# MCU098_04_XDS110-ET_EnergyTrace.net
KiCad netlist of a schematic drawn in Altium Designer
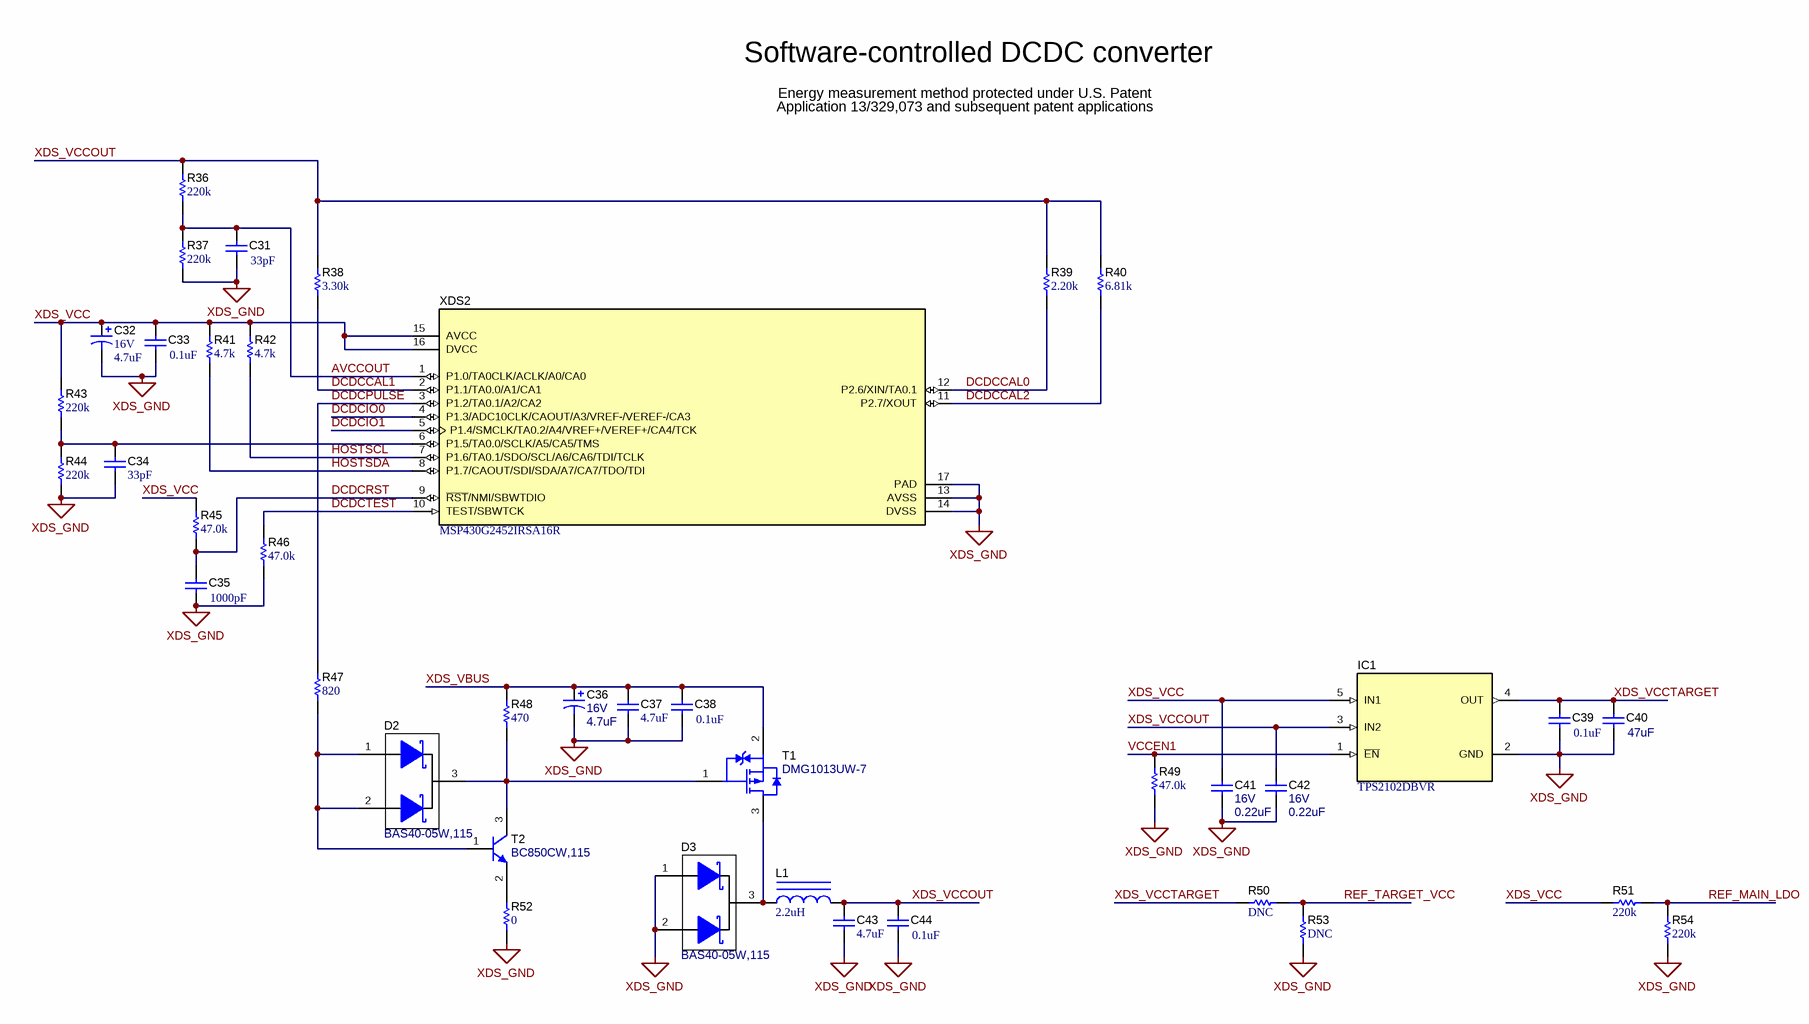
[diagram p0: MCU098_04_XDS110-ET_EnergyTrace.SchDoc]

(export (version "E")
  (design (tool "Eeschema 10.0.6"))
  (components
    (comp (ref "C31")
      (value "GRM1555C1H330JA01D")
      (footprint "0402")
      (description "CAP, CERM, 33 pF, 50 V, +/- 5%, C0G/NP0, 0402")
      (fields
        (field (name "MANUFACTURER") "MuRata")
        (field (name "VALUEDISPLAYED") "33pF")
        (field (name "PUBLISHER") "Texas Instruments")
      )
      (libsource (lib "Altium Vault - TI") (part "Capacitor"))
    )
    (comp (ref "C32")
      (value "TAJA475K016RNJ")
      (footprint "3216-18")
      (description "CAP, TA, 4.7 uF, 16 V, +/- 10%, 4 ohm, SMD")
      (fields
        (field (name "MANUFACTURER") "AVX")
        (field (name "VDC_V") "16V")
        (field (name "VALUEDISPLAYED") "4.7uF")
        (field (name "PUBLISHER") "Texas Instruments")
      )
      (libsource (lib "Altium Vault - TI") (part "Cap_Polarized"))
    )
    (comp (ref "C33")
      (value "GRM155R70J104KA01D")
      (footprint "0402")
      (description "CAP, CERM, 0.1 uF, 6.3 V, +/- 10%, X7R, 0402")
      (fields
        (field (name "MANUFACTURER") "MuRata")
        (field (name "VALUEDISPLAYED") "0.1uF")
        (field (name "PUBLISHER") "Texas Instruments")
      )
      (libsource (lib "Altium Vault - TI") (part "Capacitor"))
    )
    (comp (ref "C34")
      (value "GRM1555C1H330JA01D")
      (footprint "0402")
      (description "CAP, CERM, 33 pF, 50 V, +/- 5%, C0G/NP0, 0402")
      (fields
        (field (name "MANUFACTURER") "MuRata")
        (field (name "VALUEDISPLAYED") "33pF")
        (field (name "PUBLISHER") "Texas Instruments")
      )
      (libsource (lib "Altium Vault - TI") (part "Capacitor"))
    )
    (comp (ref "C35")
      (value "GCM155R71H102KA37D")
      (footprint "0402")
      (description "CAP, CERM, 1000 pF, 50 V, +/- 10%, X7R, AEC-Q200 Grade 1, 0402")
      (fields
        (field (name "MANUFACTURER") "MuRata")
        (field (name "VALUEDISPLAYED") "1000pF")
        (field (name "PUBLISHER") "Texas Instruments")
      )
      (libsource (lib "Altium Vault - TI") (part "Capacitor"))
    )
    (comp (ref "C36")
      (value "TAJA475K016RNJ")
      (footprint "3216-18")
      (description "CAP, TA, 4.7 uF, 16 V, +/- 10%, 4 ohm, SMD")
      (fields
        (field (name "MANUFACTURER") "AVX")
        (field (name "VDC_V") "16V")
        (field (name "VALUEDISPLAYED") "4.7uF")
        (field (name "PUBLISHER") "Texas Instruments")
      )
      (libsource (lib "Altium Vault - TI") (part "Cap_Polarized"))
    )
    (comp (ref "C37")
      (value "GRM188R61C475KAAJ")
      (footprint "0603")
      (description "CAP, CERM, 4.7 uF, 16 V, +/- 10%, X5R, 0603")
      (fields
        (field (name "MANUFACTURER") "MuRata")
        (field (name "VALUEDISPLAYED") "4.7uF")
        (field (name "PUBLISHER") "Texas Instruments")
      )
      (libsource (lib "Altium Vault - TI") (part "Capacitor"))
    )
    (comp (ref "C38")
      (value "GRM155R70J104KA01D")
      (footprint "0402")
      (description "CAP, CERM, 0.1 uF, 6.3 V, +/- 10%, X7R, 0402")
      (fields
        (field (name "MANUFACTURER") "MuRata")
        (field (name "VALUEDISPLAYED") "0.1uF")
        (field (name "PUBLISHER") "Texas Instruments")
      )
      (libsource (lib "Altium Vault - TI") (part "Capacitor"))
    )
    (comp (ref "C39")
      (value "GRM155R70J104KA01D")
      (footprint "0402")
      (description "CAP, CERM, 0.1 uF, 6.3 V, +/- 10%, X7R, 0402")
      (fields
        (field (name "MANUFACTURER") "MuRata")
        (field (name "VALUEDISPLAYED") "0.1uF")
        (field (name "PUBLISHER") "Texas Instruments")
      )
      (libsource (lib "Altium Vault - TI") (part "Capacitor"))
    )
    (comp (ref "C40")
      (value "GRM188R60J476ME15D")
      (footprint "0603")
      (description "CAP, CERM, 47 uF, 6.3 V, +/- 20%, X5R, 0603")
      (fields
        (field (name "MANUFACTURER") "MuRata")
        (field (name "VALUEDISPLAYED") "47uF")
        (field (name "PUBLISHER") "Texas Instruments")
      )
      (libsource (lib "Altium Vault - TI") (part "Capacitor"))
    )
    (comp (ref "C41")
      (value "GRM155R71C224KA12D")
      (footprint "0402")
      (description "CAP, CERM, 0.22 uF, 16 V, +/- 10%, X7R, 0402")
      (fields
        (field (name "MANUFACTURER") "MuRata")
        (field (name "VDC_V") "16V")
        (field (name "VALUEDISPLAYED") "0.22uF")
        (field (name "PUBLISHER") "Texas Instruments")
      )
      (libsource (lib "Altium Vault - TI") (part "Capacitor"))
    )
    (comp (ref "C42")
      (value "GRM155R71C224KA12D")
      (footprint "0402")
      (description "CAP, CERM, 0.22 uF, 16 V, +/- 10%, X7R, 0402")
      (fields
        (field (name "MANUFACTURER") "MuRata")
        (field (name "VDC_V") "16V")
        (field (name "VALUEDISPLAYED") "0.22uF")
        (field (name "PUBLISHER") "Texas Instruments")
      )
      (libsource (lib "Altium Vault - TI") (part "Capacitor"))
    )
    (comp (ref "C43")
      (value "GRM188R61C475KAAJ")
      (footprint "0603")
      (description "CAP, CERM, 4.7 uF, 16 V, +/- 10%, X5R, 0603")
      (fields
        (field (name "MANUFACTURER") "MuRata")
        (field (name "VALUEDISPLAYED") "4.7uF")
        (field (name "PUBLISHER") "Texas Instruments")
      )
      (libsource (lib "Altium Vault - TI") (part "Capacitor"))
    )
    (comp (ref "C44")
      (value "GRM155R70J104KA01D")
      (footprint "0402")
      (description "CAP, CERM, 0.1 uF, 6.3 V, +/- 10%, X7R, 0402")
      (fields
        (field (name "MANUFACTURER") "MuRata")
        (field (name "VALUEDISPLAYED") "0.1uF")
        (field (name "PUBLISHER") "Texas Instruments")
      )
      (libsource (lib "Altium Vault - TI") (part "Capacitor"))
    )
    (comp (ref "D2")
      (value "BAS40-05W,115")
      (footprint "SOT-323")
      (description "Diode, Schottky, 40 V, 0.12 A, AEC-Q101, SOT-323")
      (fields (field (name "MANUFACTURER") "Nexperia") (field (name "PUBLISHER") "Texas Instruments"))
      (libsource (lib "Altium Vault - TI") (part "DIODE_SCHOTTKY_A1C3_A2C3"))
    )
    (comp (ref "D3")
      (value "BAS40-05W,115")
      (footprint "SOT-323")
      (description "Diode, Schottky, 40 V, 0.12 A, AEC-Q101, SOT-323")
      (fields (field (name "MANUFACTURER") "Nexperia") (field (name "PUBLISHER") "Texas Instruments"))
      (libsource (lib "Altium Vault - TI") (part "DIODE_SCHOTTKY_A1C3_A2C3"))
    )
    (comp (ref "IC1")
      (value "TPS2102DBVR")
      (footprint "DBV0005A_N")
      (fields
        (field (name "ALTERNATE PARTNUMBER") "TPS2102DBVT")
        (field (name "MANUFACTURER") "Texas Instruments")
        (field (name "PARTNUMBER") "TPS2102DBVR")
        (field (name "PUBLISHER") "Texas Instruments")
      )
      (libsource (lib "Altium Vault - TI") (part "TPS2102DBV"))
    )
    (comp (ref "L1")
      (value "CBC2518T2R2M")
      (footprint "CBC2518")
      (description "Inductor, Wirewound, Ceramic, 2.2 uH, 0.89 A, 0.13 ohm, SMD")
      (fields
        (field (name "MANUFACTURER") "Taiyo Yuden")
        (field (name "VALUEDISPLAYED") "2.2uH")
        (field (name "PUBLISHER") "Texas Instruments")
      )
      (libsource (lib "Altium Vault - TI") (part "Inductor_Iron"))
    )
    (comp (ref "R36")
      (value "RC0402FR-07220KL")
      (footprint "0402")
      (description "RES, 220 k, 1%, 0.0625 W, 0402")
      (fields
        (field (name "MANUFACTURER") "Yageo America")
        (field (name "VALUEDISPLAYED") "220k")
        (field (name "PUBLISHER") "Texas Instruments")
      )
      (libsource (lib "Altium Vault - TI") (part "Resistor"))
    )
    (comp (ref "R37")
      (value "RC0402FR-07220KL")
      (footprint "0402")
      (description "RES, 220 k, 1%, 0.0625 W, 0402")
      (fields
        (field (name "MANUFACTURER") "Yageo America")
        (field (name "VALUEDISPLAYED") "220k")
        (field (name "PUBLISHER") "Texas Instruments")
      )
      (libsource (lib "Altium Vault - TI") (part "Resistor"))
    )
    (comp (ref "R38")
      (value "ERJ-2RKF3301X")
      (footprint "0402")
      (description "RES, 3.30 k, 1%, 0.1 W, AEC-Q200 Grade 0, 0402")
      (fields
        (field (name "MANUFACTURER") "Panasonic")
        (field (name "VALUEDISPLAYED") "3.30k")
        (field (name "PUBLISHER") "Texas Instruments")
      )
      (libsource (lib "Altium Vault - TI") (part "Resistor"))
    )
    (comp (ref "R39")
      (value "CRCW04022K20FKED")
      (footprint "0402")
      (description "RES, 2.20 k, 1%, 0.063 W, 0402")
      (fields
        (field (name "MANUFACTURER") "Vishay-Dale")
        (field (name "VALUEDISPLAYED") "2.20k")
        (field (name "PUBLISHER") "Texas Instruments")
      )
      (libsource (lib "Altium Vault - TI") (part "Resistor"))
    )
    (comp (ref "R40")
      (value "CRCW04026K81FKED")
      (footprint "0402")
      (description "RES, 6.81 k, 1%, 0.063 W, 0402")
      (fields
        (field (name "MANUFACTURER") "Vishay-Dale")
        (field (name "VALUEDISPLAYED") "6.81k")
        (field (name "PUBLISHER") "Texas Instruments")
      )
      (libsource (lib "Altium Vault - TI") (part "Resistor"))
    )
    (comp (ref "R41")
      (value "CRCW04024K70JNED")
      (footprint "0402")
      (description "RES, 4.7 k, 5%, 0.063 W, 0402")
      (fields
        (field (name "MANUFACTURER") "Vishay-Dale")
        (field (name "VALUEDISPLAYED") "4.7k")
        (field (name "PUBLISHER") "Texas Instruments")
      )
      (libsource (lib "Altium Vault - TI") (part "Resistor"))
    )
    (comp (ref "R42")
      (value "CRCW04024K70JNED")
      (footprint "0402")
      (description "RES, 4.7 k, 5%, 0.063 W, 0402")
      (fields
        (field (name "MANUFACTURER") "Vishay-Dale")
        (field (name "VALUEDISPLAYED") "4.7k")
        (field (name "PUBLISHER") "Texas Instruments")
      )
      (libsource (lib "Altium Vault - TI") (part "Resistor"))
    )
    (comp (ref "R43")
      (value "RC0402FR-07220KL")
      (footprint "0402")
      (description "RES, 220 k, 1%, 0.0625 W, 0402")
      (fields
        (field (name "MANUFACTURER") "Yageo America")
        (field (name "VALUEDISPLAYED") "220k")
        (field (name "PUBLISHER") "Texas Instruments")
      )
      (libsource (lib "Altium Vault - TI") (part "Resistor"))
    )
    (comp (ref "R44")
      (value "RC0402FR-07220KL")
      (footprint "0402")
      (description "RES, 220 k, 1%, 0.0625 W, 0402")
      (fields
        (field (name "MANUFACTURER") "Yageo America")
        (field (name "VALUEDISPLAYED") "220k")
        (field (name "PUBLISHER") "Texas Instruments")
      )
      (libsource (lib "Altium Vault - TI") (part "Resistor"))
    )
    (comp (ref "R45")
      (value "RC0402FR-0747KL")
      (footprint "0402")
      (description "RES, 47.0 k, 1%, 0.0625 W, 0402")
      (fields
        (field (name "MANUFACTURER") "Yageo America")
        (field (name "VALUEDISPLAYED") "47.0k")
        (field (name "PUBLISHER") "Texas Instruments")
      )
      (libsource (lib "Altium Vault - TI") (part "Resistor"))
    )
    (comp (ref "R46")
      (value "RC0402FR-0747KL")
      (footprint "0402")
      (description "RES, 47.0 k, 1%, 0.0625 W, 0402")
      (fields
        (field (name "MANUFACTURER") "Yageo America")
        (field (name "VALUEDISPLAYED") "47.0k")
        (field (name "PUBLISHER") "Texas Instruments")
      )
      (libsource (lib "Altium Vault - TI") (part "Resistor"))
    )
    (comp (ref "R47")
      (value "RC0402FR-07820RL")
      (footprint "0402")
      (description "RES, 820, 1%, 0.063 W, 0402")
      (fields
        (field (name "MANUFACTURER") "Yageo America")
        (field (name "VALUEDISPLAYED") "820")
        (field (name "PUBLISHER") "Texas Instruments")
      )
      (libsource (lib "Altium Vault - TI") (part "Resistor"))
    )
    (comp (ref "R48")
      (value "CRCW0402470RJNED")
      (footprint "0402")
      (description "RES, 470, 5%, 0.063 W, 0402")
      (fields
        (field (name "MANUFACTURER") "Vishay-Dale")
        (field (name "VALUEDISPLAYED") "470")
        (field (name "PUBLISHER") "Texas Instruments")
      )
      (libsource (lib "Altium Vault - TI") (part "Resistor"))
    )
    (comp (ref "R49")
      (value "RC0402FR-0747KL")
      (footprint "0402")
      (description "RES, 47.0 k, 1%, 0.0625 W, 0402")
      (fields
        (field (name "MANUFACTURER") "Yageo America")
        (field (name "VALUEDISPLAYED") "47.0k")
        (field (name "PUBLISHER") "Texas Instruments")
      )
      (libsource (lib "Altium Vault - TI") (part "Resistor"))
    )
    (comp (ref "R50")
      (value "RC0402FR-07220KL")
      (footprint "0402")
      (description "RES, 220 k, 1%, 0.0625 W, 0402")
      (fields
        (field (name "MANUFACTURER") "Yageo America")
        (field (name "VALUEDISPLAYED") "DNC")
        (field (name "PUBLISHER") "Texas Instruments")
      )
      (libsource (lib "Altium Vault - TI") (part "Resistor"))
    )
    (comp (ref "R51")
      (value "RC0402FR-07220KL")
      (footprint "0402")
      (description "RES, 220 k, 1%, 0.0625 W, 0402")
      (fields
        (field (name "MANUFACTURER") "Yageo America")
        (field (name "VALUEDISPLAYED") "220k")
        (field (name "PUBLISHER") "Texas Instruments")
      )
      (libsource (lib "Altium Vault - TI") (part "Resistor"))
    )
    (comp (ref "R52")
      (value "RC0603JR-070RL")
      (footprint "0603")
      (description "RES, 0, 5%, 0.1 W, 0603")
      (fields (field (name "MANUFACTURER") "Yageo") (field (name "VALUEDISPLAYED") "0"))
      (libsource (lib "Altium Vault - TI") (part "Resistor"))
    )
    (comp (ref "R53")
      (value "RC0402FR-07220KL")
      (footprint "0402")
      (description "RES, 220 k, 1%, 0.0625 W, 0402")
      (fields
        (field (name "MANUFACTURER") "Yageo America")
        (field (name "VALUEDISPLAYED") "DNC")
        (field (name "PUBLISHER") "Texas Instruments")
      )
      (libsource (lib "Altium Vault - TI") (part "Resistor"))
    )
    (comp (ref "R54")
      (value "RC0402FR-07220KL")
      (footprint "0402")
      (description "RES, 220 k, 1%, 0.0625 W, 0402")
      (fields
        (field (name "MANUFACTURER") "Yageo America")
        (field (name "VALUEDISPLAYED") "220k")
        (field (name "PUBLISHER") "Texas Instruments")
      )
      (libsource (lib "Altium Vault - TI") (part "Resistor"))
    )
    (comp (ref "T1")
      (value "DMG1013UW-7")
      (footprint "SOT-323")
      (description "MOSFET, P-CH, -20 V, -0.82 A, SOT-323")
      (fields (field (name "MANUFACTURER") "Diodes Inc.") (field (name "PUBLISHER") "Texas Instruments"))
      (libsource (lib "Altium Vault - TI") (part "MOSFET_P_D3G1S2_PD"))
    )
    (comp (ref "T2")
      (value "BC850CW,115")
      (footprint "SOT-323")
      (description "Transistor, NPN, 45 V, 0.1 A, SOT-323")
      (fields
        (field (name "MANUFACTURER") "NXP Semiconductor")
        (field (name "PUBLISHER") "Texas Instruments")
      )
      (libsource (lib "Altium Vault - TI") (part "BJT_NPN_C3B1E2"))
    )
    (comp (ref "XDS2")
      (value "MSP430G2452IRSA16R")
      (footprint "RSA0016B")
      (description "MSP430G2x52, MSP430G2x12 Mixed Signal Microcontroller, RSA0016B (VQFN-16)")
      (fields
        (field (name "PARTNUMBER") "MSP430G2452IRSA16R")
        (field (name "MANUFACTURER") "Texas Instruments")
        (field (name "ALTERNATE PARTNUMBER") "MSP430G2452IRSA16T")
      )
      (libsource (lib "Altium Vault - TI") (part "MSP430G2452IRSA"))
    )
  )
  (nets
    (net (code "1") (name "/AVCCOUT") (class "Default")
      (node (ref "C31") (pin "1") (pinfunction "1_1") (pintype "passive"))
      (node (ref "R36") (pin "1") (pinfunction "1_1") (pintype "passive"))
      (node (ref "R37") (pin "2") (pinfunction "2_2") (pintype "passive"))
      (node (ref "XDS2") (pin "1") (pinfunction "P1.0/TA0CLK/ACLK/A0/CA0_1") (pintype "bidirectional"))
    )
    (net (code "2") (name "/DCDCCAL0") (class "Default")
      (node (ref "R39") (pin "1") (pinfunction "1_1") (pintype "passive"))
      (node (ref "XDS2") (pin "12") (pinfunction "P2.6/XIN/TA0.1_12") (pintype "bidirectional"))
    )
    (net (code "3") (name "/DCDCCAL1") (class "Default")
      (node (ref "R38") (pin "1") (pinfunction "1_1") (pintype "passive"))
      (node (ref "XDS2") (pin "2") (pinfunction "P1.1/TA0.0/A1/CA1_2") (pintype "bidirectional"))
    )
    (net (code "4") (name "/DCDCCAL2") (class "Default")
      (node (ref "R40") (pin "1") (pinfunction "1_1") (pintype "passive"))
      (node (ref "XDS2") (pin "11") (pinfunction "P2.7/XOUT_11") (pintype "bidirectional"))
    )
    (net (code "5") (name "/DCDCIO0") (class "Default")
      (node (ref "XDS2") (pin "4") (pinfunction "P1.3/ADC10CLK/CAOUT/A3/VREF-/VEREF-/CA3_4") (pintype "bidirectional"))
    )
    (net (code "6") (name "/DCDCIO1") (class "Default")
      (node (ref "XDS2") (pin "5") (pinfunction "P1.4/SMCLK/TA0.2/A4/VREF+/VEREF+/CA4/TCK_5") (pintype "bidirectional"))
    )
    (net (code "7") (name "/DCDCPULSE") (class "Default")
      (node (ref "R47") (pin "2") (pinfunction "2_2") (pintype "passive"))
      (node (ref "XDS2") (pin "3") (pinfunction "P1.2/TA0.1/A2/CA2_3") (pintype "bidirectional"))
    )
    (net (code "8") (name "/DCDCRST") (class "Default")
      (node (ref "C35") (pin "1") (pinfunction "1_1") (pintype "passive"))
      (node (ref "R45") (pin "1") (pinfunction "1_1") (pintype "passive"))
      (node (ref "XDS2") (pin "9") (pinfunction "~{RST}/NMI/SBWTDIO_9") (pintype "bidirectional"))
    )
    (net (code "9") (name "/DCDCTEST") (class "Default")
      (node (ref "R46") (pin "2") (pinfunction "2_2") (pintype "passive"))
      (node (ref "XDS2") (pin "10") (pinfunction "TEST/SBWTCK_10") (pintype "input"))
    )
    (net (code "10") (name "/HOSTSCL") (class "Default")
      (node (ref "R42") (pin "1") (pinfunction "1_1") (pintype "passive"))
      (node (ref "XDS2") (pin "7") (pinfunction "P1.6/TA0.1/SDO/SCL/A6/CA6/TDI/TCLK_7") (pintype "bidirectional"))
    )
    (net (code "11") (name "/HOSTSDA") (class "Default")
      (node (ref "R41") (pin "1") (pinfunction "1_1") (pintype "passive"))
      (node (ref "XDS2") (pin "8") (pinfunction "P1.7/CAOUT/SDI/SDA/A7/CA7/TDO/TDI_8") (pintype "bidirectional"))
    )
    (net (code "12") (name "/REF_MAIN_LDO") (class "Default")
      (node (ref "R51") (pin "1") (pinfunction "1_1") (pintype "passive"))
      (node (ref "R54") (pin "2") (pinfunction "2_2") (pintype "passive"))
    )
    (net (code "13") (name "/REF_TARGET_VCC") (class "Default")
      (node (ref "R50") (pin "1") (pinfunction "1_1") (pintype "passive"))
      (node (ref "R53") (pin "2") (pinfunction "2_2") (pintype "passive"))
    )
    (net (code "14") (name "/VCCEN1") (class "Default")
      (node (ref "IC1") (pin "1") (pinfunction "EN_1") (pintype "input"))
      (node (ref "R49") (pin "2") (pinfunction "2_2") (pintype "passive"))
    )
    (net (code "15") (name "/XDS_VBUS") (class "Default")
      (node (ref "C36") (pin "1") (pinfunction "+_1") (pintype "passive"))
      (node (ref "C37") (pin "2") (pinfunction "2_2") (pintype "passive"))
      (node (ref "C38") (pin "1") (pinfunction "1_1") (pintype "passive"))
      (node (ref "R48") (pin "2") (pinfunction "2_2") (pintype "passive"))
      (node (ref "T1") (pin "2") (pinfunction "S_2") (pintype "passive"))
    )
    (net (code "16") (name "/XDS_VCC") (class "Default")
      (node (ref "C32") (pin "1") (pinfunction "+_1") (pintype "passive"))
      (node (ref "C33") (pin "1") (pinfunction "1_1") (pintype "passive"))
      (node (ref "C41") (pin "1") (pinfunction "1_1") (pintype "passive"))
      (node (ref "IC1") (pin "5") (pinfunction "IN1_5") (pintype "input"))
      (node (ref "R41") (pin "2") (pinfunction "2_2") (pintype "passive"))
      (node (ref "R42") (pin "2") (pinfunction "2_2") (pintype "passive"))
      (node (ref "R43") (pin "2") (pinfunction "2_2") (pintype "passive"))
      (node (ref "R45") (pin "2") (pinfunction "2_2") (pintype "passive"))
      (node (ref "R51") (pin "2") (pinfunction "2_2") (pintype "passive"))
      (node (ref "XDS2") (pin "15") (pinfunction "AVCC_15") (pintype "power_in"))
      (node (ref "XDS2") (pin "16") (pinfunction "DVCC_16") (pintype "power_in"))
    )
    (net (code "17") (name "/XDS_VCCOUT") (class "Default")
      (node (ref "C42") (pin "1") (pinfunction "1_1") (pintype "passive"))
      (node (ref "C43") (pin "2") (pinfunction "2_2") (pintype "passive"))
      (node (ref "C44") (pin "1") (pinfunction "1_1") (pintype "passive"))
      (node (ref "IC1") (pin "3") (pinfunction "IN2_3") (pintype "input"))
      (node (ref "L1") (pin "2") (pinfunction "2_2") (pintype "passive"))
      (node (ref "R36") (pin "2") (pinfunction "2_2") (pintype "passive"))
      (node (ref "R38") (pin "2") (pinfunction "2_2") (pintype "passive"))
      (node (ref "R39") (pin "2") (pinfunction "2_2") (pintype "passive"))
      (node (ref "R40") (pin "2") (pinfunction "2_2") (pintype "passive"))
    )
    (net (code "18") (name "/XDS_VCCTARGET") (class "Default")
      (node (ref "C39") (pin "1") (pinfunction "1_1") (pintype "passive"))
      (node (ref "C40") (pin "1") (pinfunction "1_1") (pintype "passive"))
      (node (ref "IC1") (pin "4") (pinfunction "OUT_4") (pintype "output"))
      (node (ref "R50") (pin "2") (pinfunction "2_2") (pintype "passive"))
    )
    (net (code "19") (name "Net-(D2-K)") (class "Default")
      (node (ref "D2") (pin "3") (pinfunction "K_3") (pintype "passive"))
      (node (ref "R48") (pin "1") (pinfunction "1_1") (pintype "passive"))
      (node (ref "T1") (pin "1") (pinfunction "G_1") (pintype "passive"))
      (node (ref "T2") (pin "3") (pinfunction "C_3") (pintype "passive"))
    )
    (net (code "20") (name "Net-(D3-K)") (class "Default")
      (node (ref "D3") (pin "3") (pinfunction "K_3") (pintype "passive"))
      (node (ref "L1") (pin "1") (pinfunction "1_1") (pintype "passive"))
      (node (ref "T1") (pin "3") (pinfunction "D_3") (pintype "passive"))
    )
    (net (code "21") (name "Net-(T2-B)") (class "Default")
      (node (ref "D2") (pin "1") (pinfunction "A_1") (pintype "passive"))
      (node (ref "D2") (pin "2") (pinfunction "A_2") (pintype "passive"))
      (node (ref "R47") (pin "1") (pinfunction "1_1") (pintype "passive"))
      (node (ref "T2") (pin "1") (pinfunction "B_1") (pintype "passive"))
    )
    (net (code "22") (name "Net-(T2-E)") (class "Default")
      (node (ref "R52") (pin "2") (pinfunction "2_2") (pintype "passive"))
      (node (ref "T2") (pin "2") (pinfunction "E_2") (pintype "passive"))
    )
    (net (code "23") (name "Net-(XDS2-P1.5{slash}TA0.0{slash}SCLK{slash}A5{slash}CA5{slash}TMS)") (class "Default")
      (node (ref "C34") (pin "1") (pinfunction "1_1") (pintype "passive"))
      (node (ref "R43") (pin "1") (pinfunction "1_1") (pintype "passive"))
      (node (ref "R44") (pin "2") (pinfunction "2_2") (pintype "passive"))
      (node (ref "XDS2") (pin "6") (pinfunction "P1.5/TA0.0/SCLK/A5/CA5/TMS_6") (pintype "bidirectional"))
    )
    (net (code "24") (name "XDS_GND") (class "Default")
      (node (ref "C31") (pin "2") (pinfunction "2_2") (pintype "passive"))
      (node (ref "C32") (pin "2") (pinfunction "-_2") (pintype "passive"))
      (node (ref "C33") (pin "2") (pinfunction "2_2") (pintype "passive"))
      (node (ref "C34") (pin "2") (pinfunction "2_2") (pintype "passive"))
      (node (ref "C35") (pin "2") (pinfunction "2_2") (pintype "passive"))
      (node (ref "C36") (pin "2") (pinfunction "-_2") (pintype "passive"))
      (node (ref "C37") (pin "1") (pinfunction "1_1") (pintype "passive"))
      (node (ref "C38") (pin "2") (pinfunction "2_2") (pintype "passive"))
      (node (ref "C39") (pin "2") (pinfunction "2_2") (pintype "passive"))
      (node (ref "C40") (pin "2") (pinfunction "2_2") (pintype "passive"))
      (node (ref "C41") (pin "2") (pinfunction "2_2") (pintype "passive"))
      (node (ref "C42") (pin "2") (pinfunction "2_2") (pintype "passive"))
      (node (ref "C43") (pin "1") (pinfunction "1_1") (pintype "passive"))
      (node (ref "C44") (pin "2") (pinfunction "2_2") (pintype "passive"))
      (node (ref "D3") (pin "1") (pinfunction "A_1") (pintype "passive"))
      (node (ref "D3") (pin "2") (pinfunction "A_2") (pintype "passive"))
      (node (ref "IC1") (pin "2") (pinfunction "GND_2") (pintype "power_in"))
      (node (ref "R37") (pin "1") (pinfunction "1_1") (pintype "passive"))
      (node (ref "R44") (pin "1") (pinfunction "1_1") (pintype "passive"))
      (node (ref "R46") (pin "1") (pinfunction "1_1") (pintype "passive"))
      (node (ref "R49") (pin "1") (pinfunction "1_1") (pintype "passive"))
      (node (ref "R52") (pin "1") (pinfunction "1_1") (pintype "passive"))
      (node (ref "R53") (pin "1") (pinfunction "1_1") (pintype "passive"))
      (node (ref "R54") (pin "1") (pinfunction "1_1") (pintype "passive"))
      (node (ref "XDS2") (pin "13") (pinfunction "AVSS_13") (pintype "power_in"))
      (node (ref "XDS2") (pin "14") (pinfunction "DVSS_14") (pintype "power_in"))
      (node (ref "XDS2") (pin "17") (pinfunction "PAD_17") (pintype "power_in"))
    )
  )
)
